# Input.net
KiCad netlist of a schematic drawn in Altium Designer
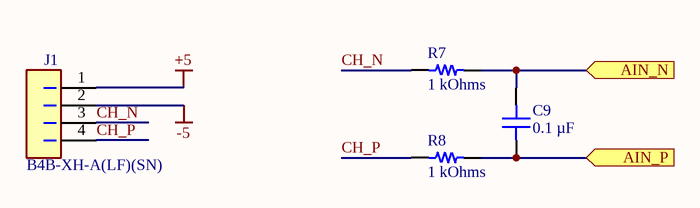
[diagram p0: Input.SchDoc]

(export (version "E")
  (design (tool "Eeschema 10.0.6"))
  (components
    (comp (ref "C9")
      (value "0.1 µF")
      (footprint "CAP 0603_1608")
      (description "CAP CER 0.1UF 50V X7R 0603")
      (fields
        (field (name "PART NUMBER") "C0603C104K5RAC7411")
        (field (name "CAPACITANCE") "0.1 µF")
        (field (name "MANUFACTURER") "KEMET")
      )
      (libsource (lib "Celestial Altium Library - altium_library") (part "Capacitor"))
    )
    (comp (ref "J1")
      (value "B4B-XH-A(LF)(SN)")
      (footprint "FP-B4B-XH-A_LF_SN-MFG")
      (description "Header for PCB; pitch 2.50mm; 4-contacts; THT male; top entry; 250V/3A")
      (libsource (lib "CLES_FACIL") (part "299a8cea1bdcbc3624fe62c390fa72c"))
    )
    (comp (ref "R7")
      (value "1 kOhms")
      (footprint "RES 0603_1608")
      (description "RES SMD 1K OHM 0.1% 1/16W 0603")
      (fields
        (field (name "PART NUMBER") "CPF0603B1K0E")
        (field (name "MANUFACTURER") "TE Connectivity Passive Product")
      )
      (libsource (lib "Celestial Altium Library - altium_library") (part "Resistor"))
    )
    (comp (ref "R8")
      (value "1 kOhms")
      (footprint "RES 0603_1608")
      (description "RES SMD 1K OHM 0.1% 1/16W 0603")
      (fields
        (field (name "PART NUMBER") "CPF0603B1K0E")
        (field (name "MANUFACTURER") "TE Connectivity Passive Product")
      )
      (libsource (lib "Celestial Altium Library - altium_library") (part "Resistor"))
    )
  )
  (nets
    (net (code "1") (name "+5") (class "Default")
      (node (ref "J1") (pin "1") (pinfunction "1_1") (pintype "passive"))
    )
    (net (code "2") (name "-5") (class "Default")
      (node (ref "J1") (pin "2") (pinfunction "2_2") (pintype "passive"))
    )
    (net (code "3") (name "/AIN_N") (class "Default")
      (node (ref "C9") (pin "2") (pinfunction "2_2") (pintype "passive"))
      (node (ref "R7") (pin "2") (pinfunction "2_2") (pintype "passive"))
    )
    (net (code "4") (name "/AIN_P") (class "Default")
      (node (ref "C9") (pin "1") (pinfunction "1_1") (pintype "passive"))
      (node (ref "R8") (pin "2") (pinfunction "2_2") (pintype "passive"))
    )
    (net (code "5") (name "/CH_N") (class "Default")
      (node (ref "J1") (pin "3") (pinfunction "3_3") (pintype "passive"))
      (node (ref "R7") (pin "1") (pinfunction "1_1") (pintype "passive"))
    )
    (net (code "6") (name "/CH_P") (class "Default")
      (node (ref "J1") (pin "4") (pinfunction "4_4") (pintype "passive"))
      (node (ref "R8") (pin "1") (pinfunction "1_1") (pintype "passive"))
    )
  )
)
